# CC2650_BLE.net
KiCad netlist of a schematic drawn in EAGLE
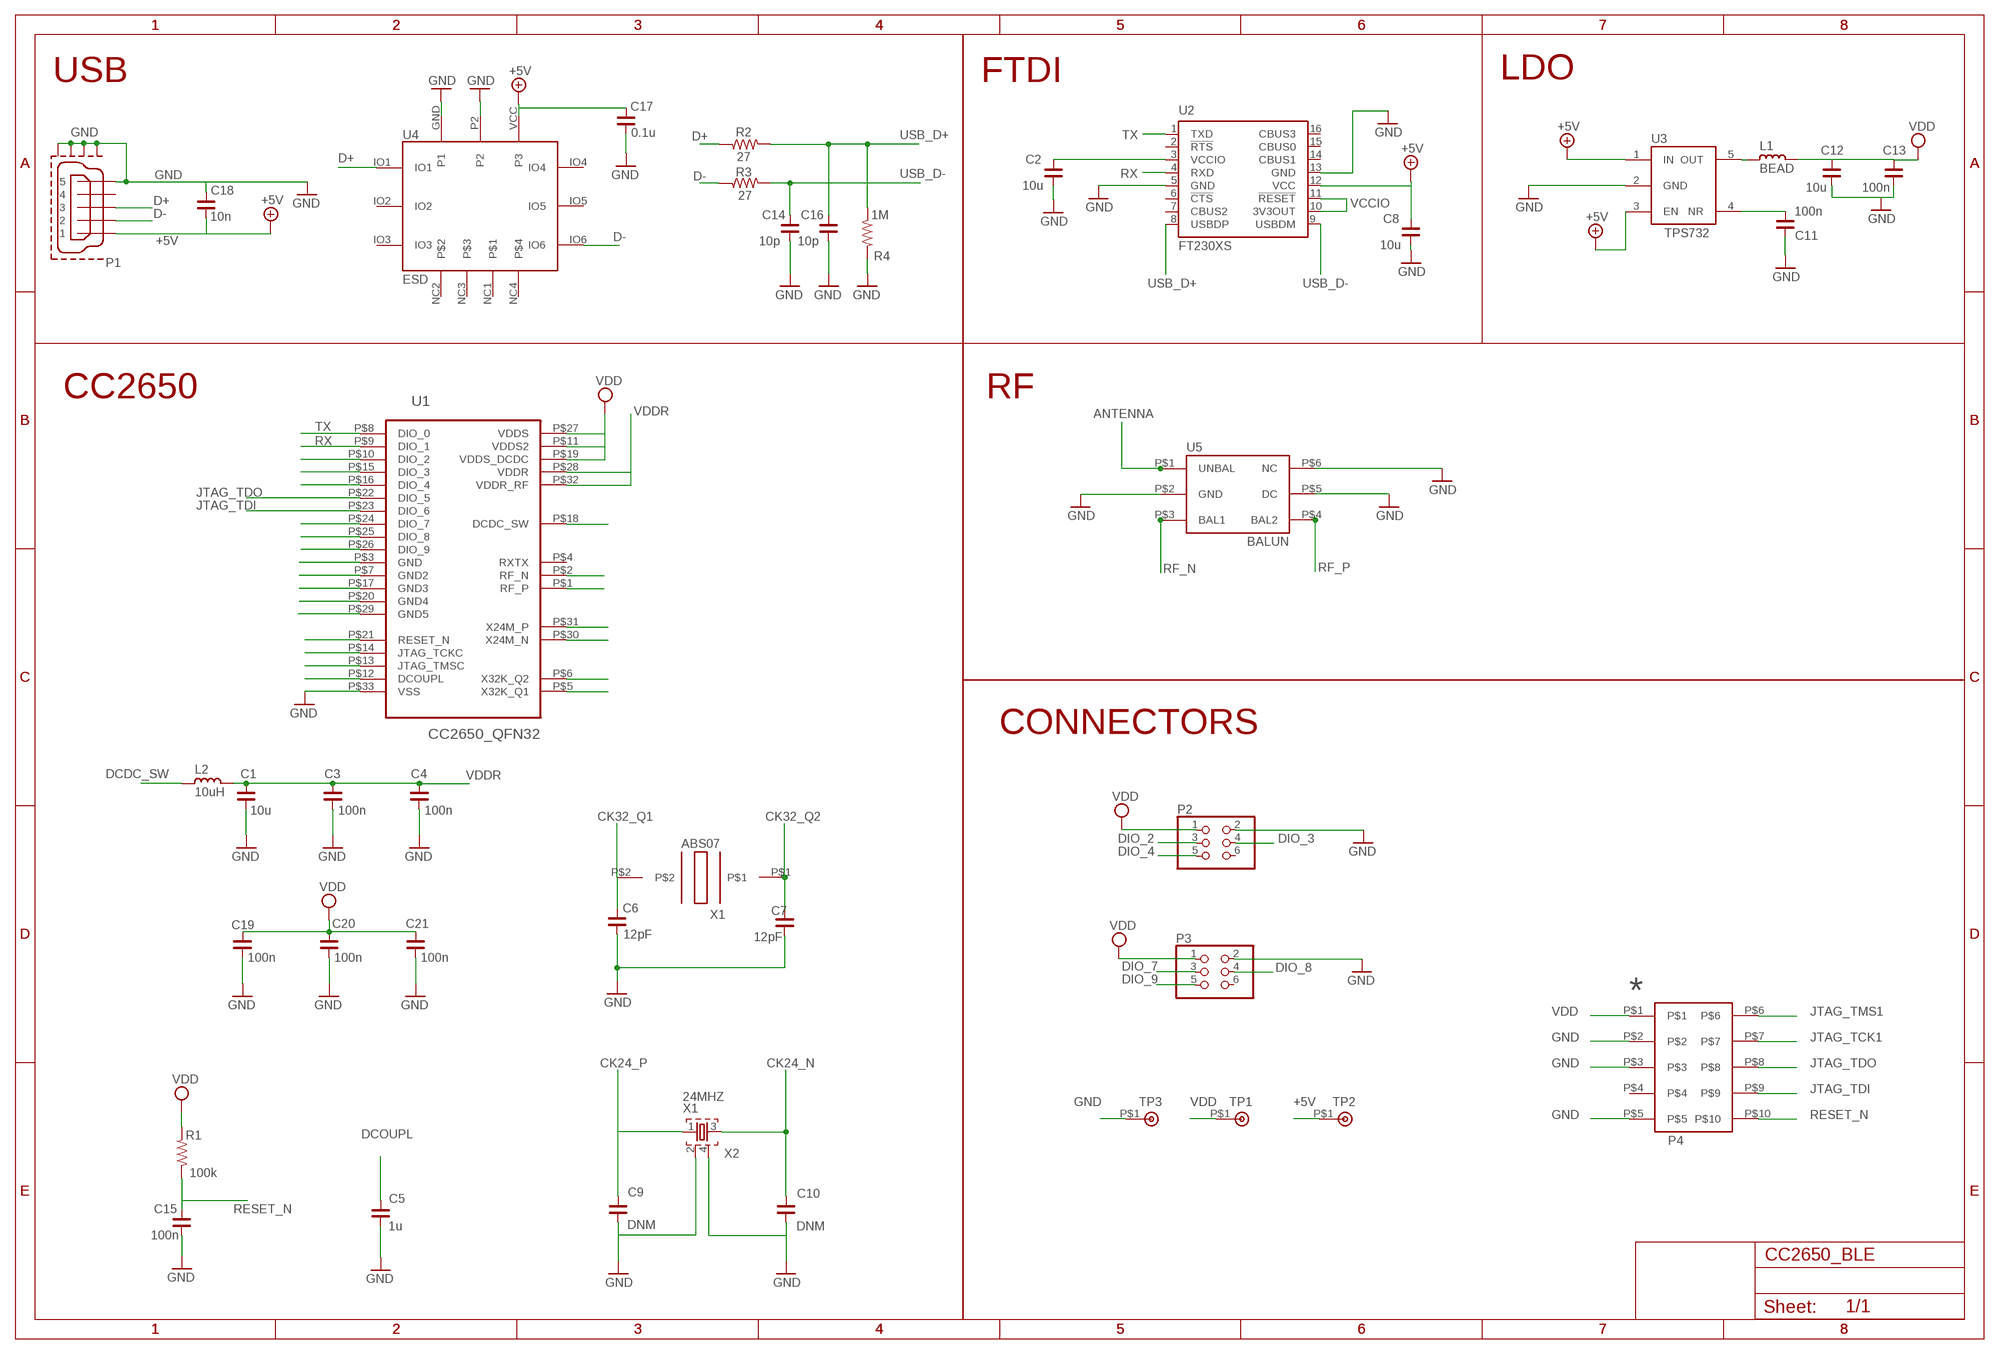
[diagram p0: schematic, sheet 1]

(export (version "E")
  (design (tool "Eeschema 10.0.6"))
  (components
    (comp (ref "24MHZ")
      (value "X1")
      (footprint "eagle-import:FA-20H")
      (libsource (lib "eagle-import") (part "FA-20H"))
    )
    (comp (ref "32KHZ")
      (value "OSC32K")
      (footprint "eagle-import:ABS07")
      (libsource (lib "eagle-import") (part "OSC32K"))
    )
    (comp (ref "C1")
      (value "10u")
      (footprint "eagle-import:C0402")
      (libsource (lib "eagle-import") (part "C_0402"))
    )
    (comp (ref "C2")
      (value "10u")
      (footprint "eagle-import:C0402")
      (libsource (lib "eagle-import") (part "C_0402"))
    )
    (comp (ref "C3")
      (value "100n")
      (footprint "eagle-import:C0402")
      (libsource (lib "eagle-import") (part "C_0402"))
    )
    (comp (ref "C4")
      (value "100n")
      (footprint "eagle-import:C0402")
      (libsource (lib "eagle-import") (part "C_0402"))
    )
    (comp (ref "C5")
      (value "1u")
      (footprint "eagle-import:C0402")
      (libsource (lib "eagle-import") (part "C_0402"))
    )
    (comp (ref "C6")
      (value "12pF")
      (footprint "eagle-import:C0402")
      (libsource (lib "eagle-import") (part "C_0402"))
    )
    (comp (ref "C7")
      (value "12pF")
      (footprint "eagle-import:C0402")
      (libsource (lib "eagle-import") (part "C_0402"))
    )
    (comp (ref "C8")
      (value "10u")
      (footprint "eagle-import:C0402")
      (libsource (lib "eagle-import") (part "C_0402"))
    )
    (comp (ref "C9")
      (value "DNM")
      (footprint "eagle-import:C0402")
      (libsource (lib "eagle-import") (part "C_0402"))
    )
    (comp (ref "C10")
      (value "DNM")
      (footprint "eagle-import:C0402")
      (libsource (lib "eagle-import") (part "C_0402"))
    )
    (comp (ref "C11")
      (value "100n")
      (footprint "eagle-import:C0402")
      (libsource (lib "eagle-import") (part "C_0402"))
    )
    (comp (ref "C12")
      (value "10u")
      (footprint "eagle-import:C0402")
      (libsource (lib "eagle-import") (part "C_0402"))
    )
    (comp (ref "C13")
      (value "100n")
      (footprint "eagle-import:C0402")
      (libsource (lib "eagle-import") (part "C_0402"))
    )
    (comp (ref "C14")
      (value "10p")
      (footprint "eagle-import:C0402")
      (libsource (lib "eagle-import") (part "C_0402"))
    )
    (comp (ref "C15")
      (value "100n")
      (footprint "eagle-import:C0402")
      (libsource (lib "eagle-import") (part "C_0402"))
    )
    (comp (ref "C16")
      (value "10p")
      (footprint "eagle-import:C0402")
      (libsource (lib "eagle-import") (part "C_0402"))
    )
    (comp (ref "C17")
      (value "0.1u")
      (footprint "eagle-import:C0402")
      (libsource (lib "eagle-import") (part "C_0402"))
    )
    (comp (ref "C18")
      (value "10n")
      (footprint "eagle-import:C0402")
      (libsource (lib "eagle-import") (part "C_0402"))
    )
    (comp (ref "C19")
      (value "100n")
      (footprint "eagle-import:C0402")
      (libsource (lib "eagle-import") (part "C_0402"))
    )
    (comp (ref "C20")
      (value "100n")
      (footprint "eagle-import:C0402")
      (libsource (lib "eagle-import") (part "C_0402"))
    )
    (comp (ref "C21")
      (value "100n")
      (footprint "eagle-import:C0402")
      (libsource (lib "eagle-import") (part "C_0402"))
    )
    (comp (ref "L1")
      (value "BEAD")
      (footprint "eagle-import:L0402")
      (libsource (lib "eagle-import") (part "L_0402"))
    )
    (comp (ref "L2")
      (value "10uH")
      (footprint "eagle-import:L0402")
      (libsource (lib "eagle-import") (part "L_0402"))
    )
    (comp (ref "P2")
      (value "PINHD-2X3")
      (footprint "eagle-import:2X03")
      (libsource (lib "eagle-import") (part "PINHD-2X3"))
    )
    (comp (ref "P3")
      (value "PINHD-2X3")
      (footprint "eagle-import:2X03")
      (libsource (lib "eagle-import") (part "PINHD-2X3"))
    )
    (comp (ref "R1")
      (value "100k")
      (footprint "eagle-import:R0603")
      (libsource (lib "eagle-import") (part "R_0603"))
    )
    (comp (ref "R2")
      (value "27")
      (footprint "eagle-import:R0603")
      (libsource (lib "eagle-import") (part "R_0603"))
    )
    (comp (ref "R3")
      (value "27")
      (footprint "eagle-import:R0603")
      (libsource (lib "eagle-import") (part "R_0603"))
    )
    (comp (ref "R4")
      (value "1M")
      (footprint "eagle-import:R0603")
      (libsource (lib "eagle-import") (part "R_0603"))
    )
    (comp (ref "TP1")
      (value "VDD")
      (footprint "eagle-import:5019_PAD")
      (libsource (lib "eagle-import") (part "TEST_POINT"))
    )
    (comp (ref "TP2")
      (value "+5V")
      (footprint "eagle-import:5019_PAD")
      (libsource (lib "eagle-import") (part "TEST_POINT"))
    )
    (comp (ref "TP3")
      (value "GND")
      (footprint "eagle-import:5019_PAD")
      (libsource (lib "eagle-import") (part "TEST_POINT"))
    )
    (comp (ref "U$3")
      (value "CC26504X4")
      (footprint "eagle-import:CC26504X4")
      (libsource (lib "eagle-import") (part "CC26504X4"))
    )
    (comp (ref "U$5")
      (value "FTSH-105-01-L-DV-K")
      (footprint "eagle-import:FTSH-105-01-L-DV-K")
      (libsource (lib "eagle-import") (part "FTSH-105-01-L-DV-K"))
    )
    (comp (ref "U2")
      (value "FT230XS")
      (footprint "eagle-import:SSOP16")
      (libsource (lib "eagle-import") (part "FT230XS"))
    )
    (comp (ref "U3")
      (value "TPS732XX")
      (footprint "eagle-import:SOT23")
      (libsource (lib "eagle-import") (part "TPS732XX"))
    )
    (comp (ref "U4")
      (value "ESD")
      (footprint "eagle-import:ESD")
      (libsource (lib "eagle-import") (part "ESD"))
    )
    (comp (ref "U5")
      (value "BALUN_NRF8001")
      (footprint "eagle-import:BALUNNORDIC")
      (libsource (lib "eagle-import") (part "BALUN_NRF8001"))
    )
    (comp (ref "USB")
      (value "MINI-USB-SHIELD-UX60-MB-5ST")
      (footprint "eagle-import:UX60-MB-5ST")
      (libsource (lib "eagle-import") (part "MINI-USB-SHIELD-UX60-MB-5ST"))
    )
  )
  (nets
    (net (code "1") (name "+5V") (class "Default")
      (node (ref "C17") (pin "2") (pinfunction "2_2") (pintype "passive"))
      (node (ref "C18") (pin "1") (pinfunction "1_1") (pintype "passive"))
      (node (ref "C8") (pin "2") (pinfunction "2_2") (pintype "passive"))
      (node (ref "TP2") (pin "P$1") (pinfunction "TEST_P$1") (pintype "bidirectional"))
      (node (ref "U2") (pin "12") (pinfunction "VCC_12") (pintype "power_in"))
      (node (ref "U3") (pin "1") (pinfunction "IN_1") (pintype "bidirectional"))
      (node (ref "U3") (pin "3") (pinfunction "EN_3") (pintype "bidirectional"))
      (node (ref "U4") (pin "VCC") (pinfunction "P3_VCC") (pintype "output"))
      (node (ref "USB") (pin "1") (pinfunction "1_1") (pintype "input"))
    )
    (net (code "2") (name "/ANTENNA") (class "Default")
      (node (ref "U5") (pin "P$1") (pinfunction "UNBAL_P$1") (pintype "bidirectional"))
    )
    (net (code "3") (name "/CK24_N") (class "Default")
      (node (ref "24MHZ") (pin "3") (pinfunction "3_3") (pintype "passive"))
      (node (ref "C10") (pin "1") (pinfunction "1_1") (pintype "passive"))
      (node (ref "U$3") (pin "P$30") (pinfunction "X24M_N_P$30") (pintype "bidirectional"))
    )
    (net (code "4") (name "/CK24_P") (class "Default")
      (node (ref "24MHZ") (pin "1") (pinfunction "1_1") (pintype "passive"))
      (node (ref "C9") (pin "1") (pinfunction "1_1") (pintype "passive"))
      (node (ref "U$3") (pin "P$31") (pinfunction "X24M_P_P$31") (pintype "bidirectional"))
    )
    (net (code "5") (name "/CK32_Q1") (class "Default")
      (node (ref "32KHZ") (pin "P$2") (pinfunction "P$2_P$2") (pintype "bidirectional"))
      (node (ref "C6") (pin "1") (pinfunction "1_1") (pintype "passive"))
      (node (ref "U$3") (pin "P$5") (pinfunction "X32K_Q1_P$5") (pintype "bidirectional"))
    )
    (net (code "6") (name "/CK32_Q2") (class "Default")
      (node (ref "32KHZ") (pin "P$1") (pinfunction "P$1_P$1") (pintype "bidirectional"))
      (node (ref "C7") (pin "1") (pinfunction "1_1") (pintype "passive"))
      (node (ref "U$3") (pin "P$6") (pinfunction "X32K_Q2_P$6") (pintype "bidirectional"))
    )
    (net (code "7") (name "/D+") (class "Default")
      (node (ref "R2") (pin "1") (pinfunction "1_1") (pintype "passive"))
      (node (ref "U4") (pin "IO1") (pinfunction "IO1_IO1") (pintype "output"))
      (node (ref "USB") (pin "3") (pinfunction "3_3") (pintype "input"))
    )
    (net (code "8") (name "/D-") (class "Default")
      (node (ref "R3") (pin "1") (pinfunction "1_1") (pintype "passive"))
      (node (ref "U4") (pin "IO6") (pinfunction "IO6_IO6") (pintype "output"))
      (node (ref "USB") (pin "2") (pinfunction "2_2") (pintype "input"))
    )
    (net (code "9") (name "/DCDC_SW") (class "Default")
      (node (ref "L2") (pin "2") (pinfunction "2_2") (pintype "passive"))
      (node (ref "U$3") (pin "P$18") (pinfunction "DCDC_SW_P$18") (pintype "bidirectional"))
    )
    (net (code "10") (name "/DCOUPL") (class "Default")
      (node (ref "C5") (pin "2") (pinfunction "2_2") (pintype "passive"))
      (node (ref "U$3") (pin "P$12") (pinfunction "DCOUPL_P$12") (pintype "bidirectional"))
    )
    (net (code "11") (name "/DIO_2") (class "Default")
      (node (ref "P2") (pin "3") (pinfunction "3_3") (pintype "passive"))
      (node (ref "U$3") (pin "P$10") (pinfunction "DIO_2_P$10") (pintype "bidirectional"))
    )
    (net (code "12") (name "/DIO_3") (class "Default")
      (node (ref "P2") (pin "4") (pinfunction "4_4") (pintype "passive"))
      (node (ref "U$3") (pin "P$15") (pinfunction "DIO_3_P$15") (pintype "input"))
    )
    (net (code "13") (name "/DIO_4") (class "Default")
      (node (ref "P2") (pin "5") (pinfunction "5_5") (pintype "passive"))
      (node (ref "U$3") (pin "P$16") (pinfunction "DIO_4_P$16") (pintype "bidirectional"))
    )
    (net (code "14") (name "/DIO_7") (class "Default")
      (node (ref "P3") (pin "3") (pinfunction "3_3") (pintype "passive"))
      (node (ref "U$3") (pin "P$24") (pinfunction "DIO_7_P$24") (pintype "bidirectional"))
    )
    (net (code "15") (name "/DIO_8") (class "Default")
      (node (ref "P3") (pin "4") (pinfunction "4_4") (pintype "passive"))
      (node (ref "U$3") (pin "P$25") (pinfunction "DIO_8_P$25") (pintype "bidirectional"))
    )
    (net (code "16") (name "/DIO_9") (class "Default")
      (node (ref "P3") (pin "5") (pinfunction "5_5") (pintype "passive"))
      (node (ref "U$3") (pin "P$26") (pinfunction "DIO_9_P$26") (pintype "bidirectional"))
    )
    (net (code "17") (name "/JTAG_TCK1") (class "Default")
      (node (ref "U$3") (pin "P$14") (pinfunction "JTAG_TCKC_P$14") (pintype "input"))
      (node (ref "U$5") (pin "P$7") (pinfunction "P$7_P$7") (pintype "bidirectional"))
    )
    (net (code "18") (name "/JTAG_TDI") (class "Default")
      (node (ref "U$3") (pin "P$23") (pinfunction "DIO_6_P$23") (pintype "bidirectional"))
      (node (ref "U$5") (pin "P$9") (pinfunction "P$9_P$9") (pintype "bidirectional"))
    )
    (net (code "19") (name "/JTAG_TDO") (class "Default")
      (node (ref "U$3") (pin "P$22") (pinfunction "DIO_5_P$22") (pintype "bidirectional"))
      (node (ref "U$5") (pin "P$8") (pinfunction "P$8_P$8") (pintype "bidirectional"))
    )
    (net (code "20") (name "/JTAG_TMS1") (class "Default")
      (node (ref "U$3") (pin "P$13") (pinfunction "JTAG_TMSC_P$13") (pintype "input"))
      (node (ref "U$5") (pin "P$6") (pinfunction "P$6_P$6") (pintype "bidirectional"))
    )
    (net (code "21") (name "/RESET_N") (class "Default")
      (node (ref "C15") (pin "2") (pinfunction "2_2") (pintype "passive"))
      (node (ref "R1") (pin "1") (pinfunction "1_1") (pintype "passive"))
      (node (ref "U$3") (pin "P$21") (pinfunction "RESET_N_P$21") (pintype "input"))
      (node (ref "U$5") (pin "P$10") (pinfunction "P$10_P$10") (pintype "bidirectional"))
    )
    (net (code "22") (name "/RF_N") (class "Default")
      (node (ref "U$3") (pin "P$2") (pinfunction "RF_N_P$2") (pintype "bidirectional"))
      (node (ref "U5") (pin "P$3") (pinfunction "BAL1_P$3") (pintype "bidirectional"))
    )
    (net (code "23") (name "/RF_P") (class "Default")
      (node (ref "U$3") (pin "P$1") (pinfunction "RF_P_P$1") (pintype "bidirectional"))
      (node (ref "U5") (pin "P$4") (pinfunction "BAL2_P$4") (pintype "bidirectional"))
    )
    (net (code "24") (name "/RX") (class "Default")
      (node (ref "U$3") (pin "P$9") (pinfunction "DIO_1_P$9") (pintype "bidirectional"))
      (node (ref "U2") (pin "4") (pinfunction "RXD_4") (pintype "input"))
    )
    (net (code "25") (name "/TX") (class "Default")
      (node (ref "U$3") (pin "P$8") (pinfunction "DIO_0_P$8") (pintype "bidirectional"))
      (node (ref "U2") (pin "1") (pinfunction "TXD_1") (pintype "output"))
    )
    (net (code "26") (name "/USB_D+") (class "Default")
      (node (ref "C16") (pin "2") (pinfunction "2_2") (pintype "passive"))
      (node (ref "R2") (pin "2") (pinfunction "2_2") (pintype "passive"))
      (node (ref "R4") (pin "1") (pinfunction "1_1") (pintype "passive"))
      (node (ref "U2") (pin "8") (pinfunction "USBDP_8") (pintype "input"))
    )
    (net (code "27") (name "/USB_D-") (class "Default")
      (node (ref "C14") (pin "2") (pinfunction "2_2") (pintype "passive"))
      (node (ref "R3") (pin "2") (pinfunction "2_2") (pintype "passive"))
      (node (ref "U2") (pin "9") (pinfunction "USBDM_9") (pintype "input"))
    )
    (net (code "28") (name "/VCCIO") (class "Default")
      (node (ref "C2") (pin "2") (pinfunction "2_2") (pintype "passive"))
      (node (ref "U2") (pin "10") (pinfunction "3V3OUT_10") (pintype "output"))
      (node (ref "U2") (pin "11") (pinfunction "~{RESET}_11") (pintype "input"))
      (node (ref "U2") (pin "3") (pinfunction "VCCIO_3") (pintype "power_in"))
    )
    (net (code "29") (name "/VDDR") (class "Default")
      (node (ref "C1") (pin "2") (pinfunction "2_2") (pintype "passive"))
      (node (ref "C3") (pin "2") (pinfunction "2_2") (pintype "passive"))
      (node (ref "C4") (pin "2") (pinfunction "2_2") (pintype "passive"))
      (node (ref "L2") (pin "1") (pinfunction "1_1") (pintype "passive"))
      (node (ref "U$3") (pin "P$28") (pinfunction "VDDR_P$28") (pintype "bidirectional"))
      (node (ref "U$3") (pin "P$32") (pinfunction "VDDR_RF_P$32") (pintype "bidirectional"))
    )
    (net (code "30") (name "GND") (class "Default")
      (node (ref "24MHZ") (pin "2") (pinfunction "2_2") (pintype "passive"))
      (node (ref "24MHZ") (pin "4") (pinfunction "4_4") (pintype "passive"))
      (node (ref "C1") (pin "1") (pinfunction "1_1") (pintype "passive"))
      (node (ref "C10") (pin "2") (pinfunction "2_2") (pintype "passive"))
      (node (ref "C11") (pin "1") (pinfunction "1_1") (pintype "passive"))
      (node (ref "C12") (pin "1") (pinfunction "1_1") (pintype "passive"))
      (node (ref "C13") (pin "1") (pinfunction "1_1") (pintype "passive"))
      (node (ref "C14") (pin "1") (pinfunction "1_1") (pintype "passive"))
      (node (ref "C15") (pin "1") (pinfunction "1_1") (pintype "passive"))
      (node (ref "C16") (pin "1") (pinfunction "1_1") (pintype "passive"))
      (node (ref "C17") (pin "1") (pinfunction "1_1") (pintype "passive"))
      (node (ref "C18") (pin "2") (pinfunction "2_2") (pintype "passive"))
      (node (ref "C19") (pin "1") (pinfunction "1_1") (pintype "passive"))
      (node (ref "C2") (pin "1") (pinfunction "1_1") (pintype "passive"))
      (node (ref "C20") (pin "1") (pinfunction "1_1") (pintype "passive"))
      (node (ref "C21") (pin "1") (pinfunction "1_1") (pintype "passive"))
      (node (ref "C3") (pin "1") (pinfunction "1_1") (pintype "passive"))
      (node (ref "C4") (pin "1") (pinfunction "1_1") (pintype "passive"))
      (node (ref "C5") (pin "1") (pinfunction "1_1") (pintype "passive"))
      (node (ref "C6") (pin "2") (pinfunction "2_2") (pintype "passive"))
      (node (ref "C7") (pin "2") (pinfunction "2_2") (pintype "passive"))
      (node (ref "C8") (pin "1") (pinfunction "1_1") (pintype "passive"))
      (node (ref "C9") (pin "2") (pinfunction "2_2") (pintype "passive"))
      (node (ref "P2") (pin "2") (pinfunction "2_2") (pintype "passive"))
      (node (ref "P3") (pin "2") (pinfunction "2_2") (pintype "passive"))
      (node (ref "R4") (pin "2") (pinfunction "2_2") (pintype "passive"))
      (node (ref "TP3") (pin "P$1") (pinfunction "TEST_P$1") (pintype "bidirectional"))
      (node (ref "U$3") (pin "P$17") (pinfunction "GND3_P$17") (pintype "bidirectional"))
      (node (ref "U$3") (pin "P$20") (pinfunction "GND4_P$20") (pintype "bidirectional"))
      (node (ref "U$3") (pin "P$3") (pinfunction "GND_P$3") (pintype "bidirectional"))
      (node (ref "U$3") (pin "P$33") (pinfunction "VSS_P$33") (pintype "power_in"))
      (node (ref "U$3") (pin "P$7") (pinfunction "GND2_P$7") (pintype "bidirectional"))
      (node (ref "U$5") (pin "P$2") (pinfunction "P$2_P$2") (pintype "bidirectional"))
      (node (ref "U$5") (pin "P$3") (pinfunction "P$3_P$3") (pintype "bidirectional"))
      (node (ref "U$5") (pin "P$5") (pinfunction "P$5_P$5") (pintype "bidirectional"))
      (node (ref "U2") (pin "13") (pinfunction "GND_13") (pintype "power_in"))
      (node (ref "U2") (pin "5") (pinfunction "GND_5") (pintype "power_in"))
      (node (ref "U3") (pin "2") (pinfunction "GND_2") (pintype "bidirectional"))
      (node (ref "U4") (pin "GND") (pinfunction "P1_GND") (pintype "output"))
      (node (ref "U4") (pin "P2") (pinfunction "P2_P2") (pintype "output"))
      (node (ref "U5") (pin "P$2") (pinfunction "GND_P$2") (pintype "bidirectional"))
      (node (ref "U5") (pin "P$5") (pinfunction "DC_P$5") (pintype "bidirectional"))
      (node (ref "U5") (pin "P$6") (pinfunction "NC_P$6") (pintype "bidirectional"))
      (node (ref "USB") (pin "5") (pinfunction "5_5") (pintype "input"))
      (node (ref "USB") (pin "M1") (pinfunction "GND1_M1") (pintype "bidirectional"))
      (node (ref "USB") (pin "M2") (pinfunction "GND2_M2") (pintype "bidirectional"))
      (node (ref "USB") (pin "M3") (pinfunction "GND3_M3") (pintype "bidirectional"))
      (node (ref "USB") (pin "M4") (pinfunction "GND4_M4") (pintype "bidirectional"))
    )
    (net (code "31") (name "Net-(U3-NR)") (class "Default")
      (node (ref "C11") (pin "2") (pinfunction "2_2") (pintype "passive"))
      (node (ref "U3") (pin "4") (pinfunction "NR_4") (pintype "bidirectional"))
    )
    (net (code "32") (name "Net-(U3-OUT)") (class "Default")
      (node (ref "L1") (pin "2") (pinfunction "2_2") (pintype "passive"))
      (node (ref "U3") (pin "5") (pinfunction "OUT_5") (pintype "bidirectional"))
    )
    (net (code "33") (name "VDD") (class "Default")
      (node (ref "C12") (pin "2") (pinfunction "2_2") (pintype "passive"))
      (node (ref "C13") (pin "2") (pinfunction "2_2") (pintype "passive"))
      (node (ref "C19") (pin "2") (pinfunction "2_2") (pintype "passive"))
      (node (ref "C20") (pin "2") (pinfunction "2_2") (pintype "passive"))
      (node (ref "C21") (pin "2") (pinfunction "2_2") (pintype "passive"))
      (node (ref "L1") (pin "1") (pinfunction "1_1") (pintype "passive"))
      (node (ref "P2") (pin "1") (pinfunction "1_1") (pintype "passive"))
      (node (ref "P3") (pin "1") (pinfunction "1_1") (pintype "passive"))
      (node (ref "R1") (pin "2") (pinfunction "2_2") (pintype "passive"))
      (node (ref "TP1") (pin "P$1") (pinfunction "TEST_P$1") (pintype "bidirectional"))
      (node (ref "U$3") (pin "P$11") (pinfunction "VDDS2_P$11") (pintype "bidirectional"))
      (node (ref "U$3") (pin "P$19") (pinfunction "VDDS_DCDC_P$19") (pintype "bidirectional"))
      (node (ref "U$3") (pin "P$27") (pinfunction "VDDS_P$27") (pintype "bidirectional"))
      (node (ref "U$5") (pin "P$1") (pinfunction "P$1_P$1") (pintype "bidirectional"))
    )
    (net (code "34") (name "unconnected-(P2-Pad6)") (class "Default")
      (node (ref "P2") (pin "6") (pinfunction "6_6") (pintype "passive"))
    )
    (net (code "35") (name "unconnected-(P3-Pad6)") (class "Default")
      (node (ref "P3") (pin "6") (pinfunction "6_6") (pintype "passive"))
    )
    (net (code "36") (name "unconnected-(U$3-GND5-PadP$29)") (class "Default")
      (node (ref "U$3") (pin "P$29") (pinfunction "GND5_P$29") (pintype "bidirectional"))
    )
    (net (code "37") (name "unconnected-(U$3-RXTX-PadP$4)") (class "Default")
      (node (ref "U$3") (pin "P$4") (pinfunction "RXTX_P$4") (pintype "bidirectional"))
    )
    (net (code "38") (name "unconnected-(U$5-PadP$4)") (class "Default")
      (node (ref "U$5") (pin "P$4") (pinfunction "P$4_P$4") (pintype "bidirectional"))
    )
    (net (code "39") (name "unconnected-(U2-CBUS0-Pad15)") (class "Default")
      (node (ref "U2") (pin "15") (pinfunction "CBUS0_15") (pintype "bidirectional"))
    )
    (net (code "40") (name "unconnected-(U2-CBUS1-Pad14)") (class "Default")
      (node (ref "U2") (pin "14") (pinfunction "CBUS1_14") (pintype "bidirectional"))
    )
    (net (code "41") (name "unconnected-(U2-CBUS2-Pad7)") (class "Default")
      (node (ref "U2") (pin "7") (pinfunction "CBUS2_7") (pintype "bidirectional"))
    )
    (net (code "42") (name "unconnected-(U2-CBUS3-Pad16)") (class "Default")
      (node (ref "U2") (pin "16") (pinfunction "CBUS3_16") (pintype "bidirectional"))
    )
    (net (code "43") (name "unconnected-(U2-~{CTS}-Pad6)") (class "Default")
      (node (ref "U2") (pin "6") (pinfunction "~{CTS}_6") (pintype "input"))
    )
    (net (code "44") (name "unconnected-(U2-~{RTS}-Pad2)") (class "Default")
      (node (ref "U2") (pin "2") (pinfunction "~{RTS}_2") (pintype "output"))
    )
    (net (code "45") (name "unconnected-(U4-P$1-PadNC1)") (class "Default")
      (node (ref "U4") (pin "NC1") (pinfunction "P$1_NC1") (pintype "bidirectional"))
    )
    (net (code "46") (name "unconnected-(U4-P$2-PadNC2)") (class "Default")
      (node (ref "U4") (pin "NC2") (pinfunction "P$2_NC2") (pintype "bidirectional"))
    )
    (net (code "47") (name "unconnected-(U4-P$3-PadNC3)") (class "Default")
      (node (ref "U4") (pin "NC3") (pinfunction "P$3_NC3") (pintype "bidirectional"))
    )
    (net (code "48") (name "unconnected-(U4-P$4-PadNC4)") (class "Default")
      (node (ref "U4") (pin "NC4") (pinfunction "P$4_NC4") (pintype "bidirectional"))
    )
    (net (code "49") (name "unconnected-(U4-PadIO2)") (class "Default")
      (node (ref "U4") (pin "IO2") (pinfunction "IO2_IO2") (pintype "output"))
    )
    (net (code "50") (name "unconnected-(U4-PadIO3)") (class "Default")
      (node (ref "U4") (pin "IO3") (pinfunction "IO3_IO3") (pintype "output"))
    )
    (net (code "51") (name "unconnected-(U4-PadIO4)") (class "Default")
      (node (ref "U4") (pin "IO4") (pinfunction "IO4_IO4") (pintype "output"))
    )
    (net (code "52") (name "unconnected-(U4-PadIO5)") (class "Default")
      (node (ref "U4") (pin "IO5") (pinfunction "IO5_IO5") (pintype "output"))
    )
    (net (code "53") (name "unconnected-(USB-Pad4)") (class "Default")
      (node (ref "USB") (pin "4") (pinfunction "4_4") (pintype "input"))
    )
  )
)
